# 03.net
KiCad netlist of a schematic drawn in Altium Designer
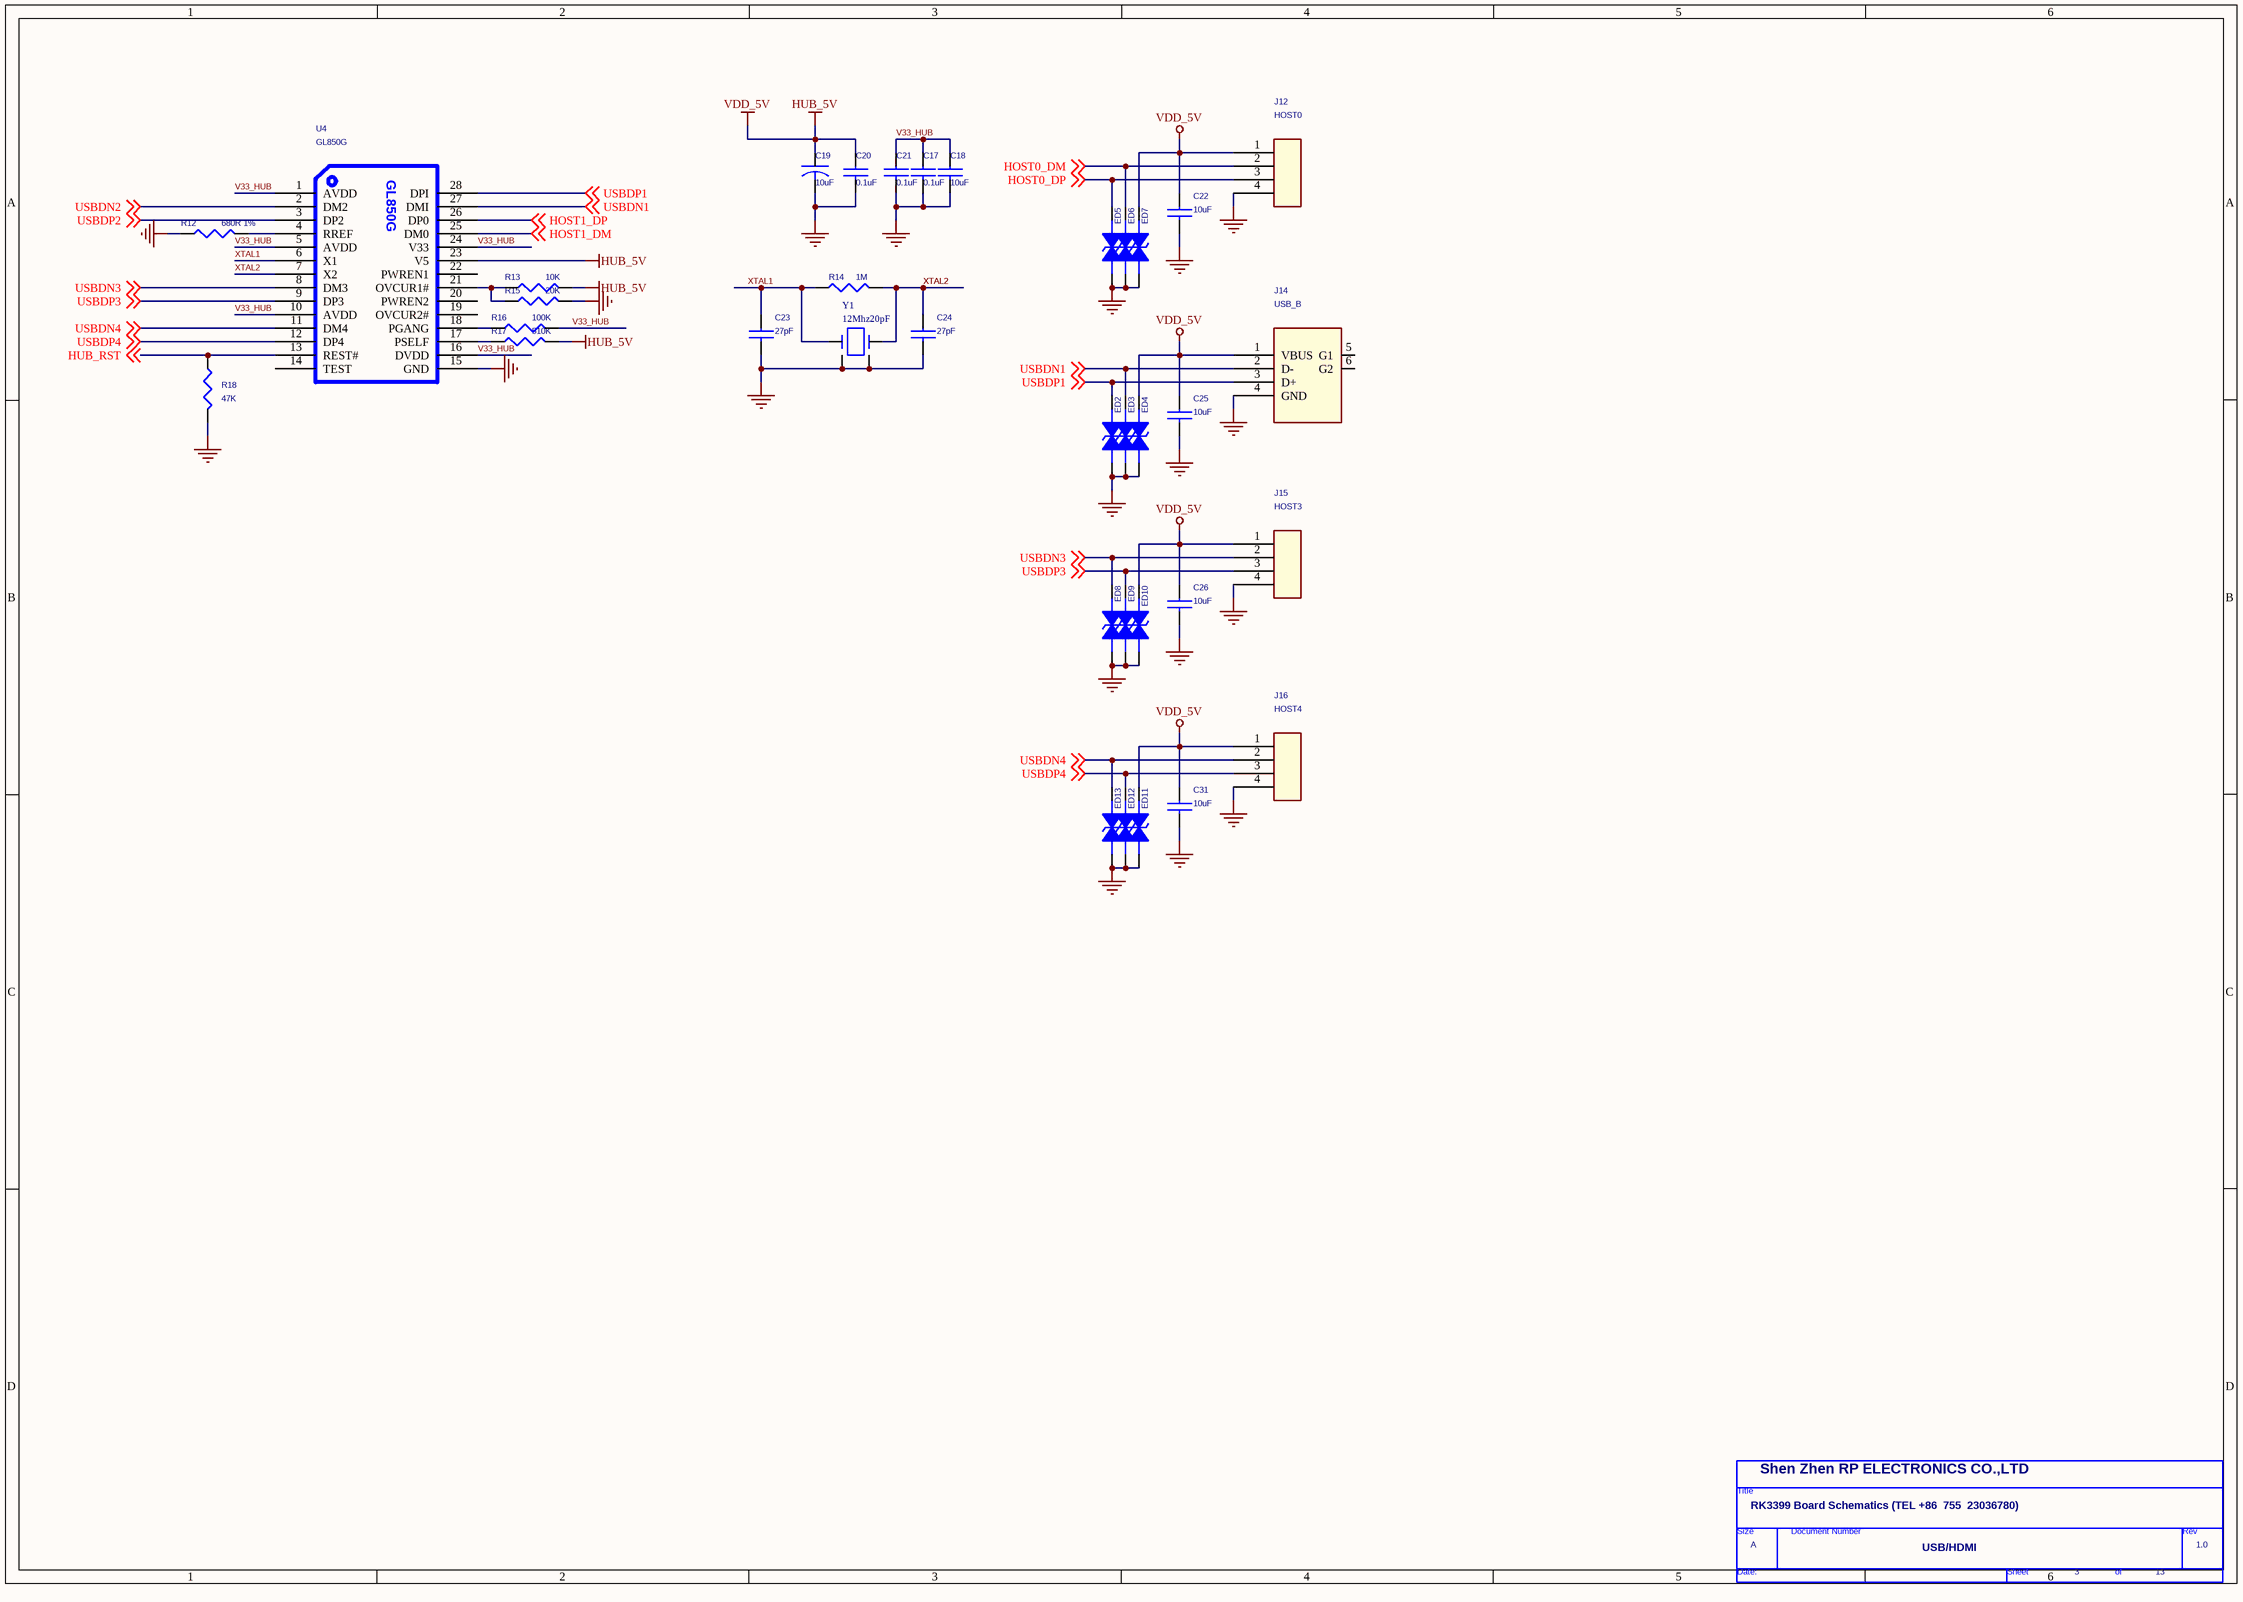
[diagram p0: 03.SchDoc]

(export (version "E")
  (design (tool "Eeschema 10.0.6"))
  (components
    (comp (ref "C17") (value "0.1uF") (footprint "0805C") (libsource (lib "*") (part "CAP NP_Dup5")))
    (comp (ref "C18") (value "10uF") (footprint "0805C") (libsource (lib "*") (part "CAP NP_Dup5")))
    (comp (ref "C19") (value "10uF") (footprint "0805C") (libsource (lib "*") (part "CAP_Dup1")))
    (comp (ref "C20") (value "0.1uF") (footprint "0805C") (libsource (lib "*") (part "CAP NP_Dup5")))
    (comp (ref "C21") (value "0.1uF") (footprint "0805C") (libsource (lib "*") (part "CAP NP_Dup5")))
    (comp (ref "C22") (value "10uF") (footprint "0805C") (libsource (lib "*") (part "CAP NP_Dup8")))
    (comp (ref "C23") (value "27pF") (footprint "0805C") (libsource (lib "*") (part "CAP NP_3_Dup1")))
    (comp (ref "C24") (value "27pF") (footprint "0805C") (libsource (lib "*") (part "CAP NP_3_Dup1")))
    (comp (ref "C25") (value "10uF") (footprint "0805C") (libsource (lib "*") (part "CAP NP_Dup8")))
    (comp (ref "C26") (value "10uF") (footprint "0805C") (libsource (lib "*") (part "CAP NP_Dup8")))
    (comp (ref "C31") (value "10uF") (footprint "0805C") (libsource (lib "*") (part "CAP NP_Dup8")))
    (comp (ref "ED2") (value "ESD") (footprint "SOD-323") (libsource (lib "*") (part "DIODE BI-DIR TRIG")))
    (comp (ref "ED3") (value "ESD") (footprint "SOD-323") (libsource (lib "*") (part "DIODE BI-DIR TRIG")))
    (comp (ref "ED4") (value "ESD") (footprint "SOD-323") (libsource (lib "*") (part "DIODE BI-DIR TRIG")))
    (comp (ref "ED5") (value "ESD") (footprint "SOD-323") (libsource (lib "*") (part "DIODE BI-DIR TRIG")))
    (comp (ref "ED6") (value "ESD") (footprint "SOD-323") (libsource (lib "*") (part "DIODE BI-DIR TRIG")))
    (comp (ref "ED7") (value "ESD") (footprint "SOD-323") (libsource (lib "*") (part "DIODE BI-DIR TRIG")))
    (comp (ref "ED8") (value "ESD") (footprint "SOD-323") (libsource (lib "*") (part "DIODE BI-DIR TRIG")))
    (comp (ref "ED9") (value "ESD") (footprint "SOD-323") (libsource (lib "*") (part "DIODE BI-DIR TRIG")))
    (comp (ref "ED10") (value "ESD") (footprint "SOD-323") (libsource (lib "*") (part "DIODE BI-DIR TRIG")))
    (comp (ref "ED11") (value "ESD") (footprint "SOD-323") (libsource (lib "*") (part "DIODE BI-DIR TRIG")))
    (comp (ref "ED12") (value "ESD") (footprint "SOD-323") (libsource (lib "*") (part "DIODE BI-DIR TRIG")))
    (comp (ref "ED13") (value "ESD") (footprint "SOD-323") (libsource (lib "*") (part "DIODE BI-DIR TRIG")))
    (comp (ref "J12") (value "HOST0") (libsource (lib "*") (part "CON4")))
    (comp (ref "J14") (value "USB_B") (libsource (lib "*") (part "USB_A_1")))
    (comp (ref "J15") (value "HOST3") (libsource (lib "*") (part "CON4")))
    (comp (ref "J16") (value "HOST4") (libsource (lib "*") (part "CON4")))
    (comp (ref "R12") (value "680R 1%") (footprint "0805") (libsource (lib "*") (part "01RES")))
    (comp (ref "R13") (value "10K") (libsource (lib "*") (part "R_1")))
    (comp (ref "R14") (value "1M") (footprint "0805") (libsource (lib "*") (part "RES_0")))
    (comp (ref "R15") (value "20K") (libsource (lib "*") (part "R_1")))
    (comp (ref "R16") (value "100K") (libsource (lib "*") (part "R_1")))
    (comp (ref "R17") (value "510K") (libsource (lib "*") (part "R_1")))
    (comp (ref "R18") (value "47K") (libsource (lib "*") (part "R_1")))
    (comp (ref "U4") (value "GL850G") (libsource (lib "*") (part "FE1_1s_SSOP28_1")))
    (comp (ref "Y1") (value "12Mhz20pF") (libsource (lib "*") (part "CRYSTAL_2")))
  )
  (nets
    (net (code "1") (name "/V33_HUB") (class "Default")
      (node (ref "C17") (pin "1") (pinfunction "1_1") (pintype "passive"))
      (node (ref "C18") (pin "1") (pinfunction "1_1") (pintype "passive"))
      (node (ref "C21") (pin "1") (pinfunction "1_1") (pintype "passive"))
      (node (ref "R16") (pin "2") (pinfunction "2_2") (pintype "passive"))
      (node (ref "U4") (pin "1") (pinfunction "AVDD_1") (pintype "power_in"))
      (node (ref "U4") (pin "10") (pinfunction "AVDD_10") (pintype "power_in"))
      (node (ref "U4") (pin "16") (pinfunction "DVDD_16") (pintype "passive"))
      (node (ref "U4") (pin "24") (pinfunction "V33_24") (pintype "passive"))
      (node (ref "U4") (pin "5") (pinfunction "AVDD_5") (pintype "power_in"))
    )
    (net (code "2") (name "/XTAL1") (class "Default")
      (node (ref "C23") (pin "1") (pinfunction "1_1") (pintype "passive"))
      (node (ref "R14") (pin "2") (pinfunction "2_2") (pintype "passive"))
      (node (ref "U4") (pin "6") (pinfunction "X1_6") (pintype "passive"))
      (node (ref "Y1") (pin "1") (pinfunction "1_1") (pintype "passive"))
    )
    (net (code "3") (name "/XTAL2") (class "Default")
      (node (ref "C24") (pin "1") (pinfunction "1_1") (pintype "passive"))
      (node (ref "R14") (pin "1") (pinfunction "1_1") (pintype "passive"))
      (node (ref "U4") (pin "7") (pinfunction "X2_7") (pintype "passive"))
      (node (ref "Y1") (pin "3") (pinfunction "3_3") (pintype "passive"))
    )
    (net (code "4") (name "GND") (class "Default")
      (node (ref "C17") (pin "2") (pinfunction "2_2") (pintype "passive"))
      (node (ref "C18") (pin "2") (pinfunction "2_2") (pintype "passive"))
      (node (ref "C19") (pin "2") (pinfunction "2_2") (pintype "passive"))
      (node (ref "C20") (pin "2") (pinfunction "2_2") (pintype "passive"))
      (node (ref "C21") (pin "2") (pinfunction "2_2") (pintype "passive"))
      (node (ref "C22") (pin "2") (pinfunction "2_2") (pintype "passive"))
      (node (ref "C23") (pin "2") (pinfunction "2_2") (pintype "passive"))
      (node (ref "C24") (pin "2") (pinfunction "2_2") (pintype "passive"))
      (node (ref "C25") (pin "2") (pinfunction "2_2") (pintype "passive"))
      (node (ref "C26") (pin "2") (pinfunction "2_2") (pintype "passive"))
      (node (ref "C31") (pin "2") (pinfunction "2_2") (pintype "passive"))
      (node (ref "ED10") (pin "2") (pinfunction "2_2") (pintype "passive"))
      (node (ref "ED11") (pin "2") (pinfunction "2_2") (pintype "passive"))
      (node (ref "ED12") (pin "2") (pinfunction "2_2") (pintype "passive"))
      (node (ref "ED13") (pin "2") (pinfunction "2_2") (pintype "passive"))
      (node (ref "ED2") (pin "2") (pinfunction "2_2") (pintype "passive"))
      (node (ref "ED3") (pin "2") (pinfunction "2_2") (pintype "passive"))
      (node (ref "ED4") (pin "2") (pinfunction "2_2") (pintype "passive"))
      (node (ref "ED5") (pin "2") (pinfunction "2_2") (pintype "passive"))
      (node (ref "ED6") (pin "2") (pinfunction "2_2") (pintype "passive"))
      (node (ref "ED7") (pin "2") (pinfunction "2_2") (pintype "passive"))
      (node (ref "ED8") (pin "2") (pinfunction "2_2") (pintype "passive"))
      (node (ref "ED9") (pin "2") (pinfunction "2_2") (pintype "passive"))
      (node (ref "J12") (pin "4") (pinfunction "4_4") (pintype "passive"))
      (node (ref "J14") (pin "4") (pinfunction "GND_4") (pintype "passive"))
      (node (ref "J15") (pin "4") (pinfunction "4_4") (pintype "passive"))
      (node (ref "J16") (pin "4") (pinfunction "4_4") (pintype "passive"))
      (node (ref "R12") (pin "1") (pinfunction "1_1") (pintype "passive"))
      (node (ref "R15") (pin "2") (pinfunction "2_2") (pintype "passive"))
      (node (ref "R18") (pin "2") (pinfunction "2_2") (pintype "passive"))
      (node (ref "U4") (pin "15") (pinfunction "GND_15") (pintype "passive"))
      (node (ref "Y1") (pin "2") (pinfunction "2_2") (pintype "passive"))
      (node (ref "Y1") (pin "4") (pinfunction "4_4") (pintype "passive"))
    )
    (net (code "5") (name "HOST0_DM") (class "Default")
      (node (ref "ED6") (pin "1") (pinfunction "1_1") (pintype "passive"))
      (node (ref "J12") (pin "2") (pinfunction "2_2") (pintype "passive"))
    )
    (net (code "6") (name "HOST0_DP") (class "Default")
      (node (ref "ED5") (pin "1") (pinfunction "1_1") (pintype "passive"))
      (node (ref "J12") (pin "3") (pinfunction "3_3") (pintype "passive"))
    )
    (net (code "7") (name "HOST1_DM") (class "Default")
      (node (ref "U4") (pin "25") (pinfunction "DM0_25") (pintype "passive"))
    )
    (net (code "8") (name "HOST1_DP") (class "Default")
      (node (ref "U4") (pin "26") (pinfunction "DP0_26") (pintype "passive"))
    )
    (net (code "9") (name "HUB_5V") (class "Default")
      (node (ref "C19") (pin "1") (pinfunction "1_1") (pintype "passive"))
      (node (ref "C20") (pin "1") (pinfunction "1_1") (pintype "passive"))
      (node (ref "C22") (pin "1") (pinfunction "1_1") (pintype "passive"))
      (node (ref "C25") (pin "1") (pinfunction "1_1") (pintype "passive"))
      (node (ref "C26") (pin "1") (pinfunction "1_1") (pintype "passive"))
      (node (ref "C31") (pin "1") (pinfunction "1_1") (pintype "passive"))
      (node (ref "ED10") (pin "1") (pinfunction "1_1") (pintype "passive"))
      (node (ref "ED11") (pin "1") (pinfunction "1_1") (pintype "passive"))
      (node (ref "ED4") (pin "1") (pinfunction "1_1") (pintype "passive"))
      (node (ref "ED7") (pin "1") (pinfunction "1_1") (pintype "passive"))
      (node (ref "J12") (pin "1") (pinfunction "1_1") (pintype "passive"))
      (node (ref "J14") (pin "1") (pinfunction "VBUS_1") (pintype "passive"))
      (node (ref "J15") (pin "1") (pinfunction "1_1") (pintype "passive"))
      (node (ref "J16") (pin "1") (pinfunction "1_1") (pintype "passive"))
      (node (ref "R13") (pin "2") (pinfunction "2_2") (pintype "passive"))
      (node (ref "R17") (pin "2") (pinfunction "2_2") (pintype "passive"))
      (node (ref "U4") (pin "23") (pinfunction "V5_23") (pintype "passive"))
    )
    (net (code "10") (name "HUB_RST") (class "Default")
      (node (ref "R18") (pin "1") (pinfunction "1_1") (pintype "passive"))
      (node (ref "U4") (pin "13") (pinfunction "REST#_13") (pintype "passive"))
    )
    (net (code "11") (name "Net-(U4-OVCUR1#)") (class "Default")
      (node (ref "R13") (pin "1") (pinfunction "1_1") (pintype "passive"))
      (node (ref "R15") (pin "1") (pinfunction "1_1") (pintype "passive"))
      (node (ref "U4") (pin "21") (pinfunction "OVCUR1#_21") (pintype "passive"))
    )
    (net (code "12") (name "Net-(U4-PGANG)") (class "Default")
      (node (ref "R16") (pin "1") (pinfunction "1_1") (pintype "passive"))
      (node (ref "U4") (pin "18") (pinfunction "PGANG_18") (pintype "passive"))
    )
    (net (code "13") (name "Net-(U4-PSELF)") (class "Default")
      (node (ref "R17") (pin "1") (pinfunction "1_1") (pintype "passive"))
      (node (ref "U4") (pin "17") (pinfunction "PSELF_17") (pintype "passive"))
    )
    (net (code "14") (name "Net-(U4-RREF)") (class "Default")
      (node (ref "R12") (pin "2") (pinfunction "2_2") (pintype "passive"))
      (node (ref "U4") (pin "4") (pinfunction "RREF_4") (pintype "passive"))
    )
    (net (code "15") (name "USBDN1") (class "Default")
      (node (ref "ED3") (pin "1") (pinfunction "1_1") (pintype "passive"))
      (node (ref "J14") (pin "2") (pinfunction "D-_2") (pintype "passive"))
      (node (ref "U4") (pin "27") (pinfunction "DMI_27") (pintype "passive"))
    )
    (net (code "16") (name "USBDN2") (class "Default")
      (node (ref "U4") (pin "2") (pinfunction "DM2_2") (pintype "passive"))
    )
    (net (code "17") (name "USBDN3") (class "Default")
      (node (ref "ED8") (pin "1") (pinfunction "1_1") (pintype "passive"))
      (node (ref "J15") (pin "2") (pinfunction "2_2") (pintype "passive"))
      (node (ref "U4") (pin "8") (pinfunction "DM3_8") (pintype "passive"))
    )
    (net (code "18") (name "USBDN4") (class "Default")
      (node (ref "ED13") (pin "1") (pinfunction "1_1") (pintype "passive"))
      (node (ref "J16") (pin "2") (pinfunction "2_2") (pintype "passive"))
      (node (ref "U4") (pin "11") (pinfunction "DM4_11") (pintype "passive"))
    )
    (net (code "19") (name "USBDP1") (class "Default")
      (node (ref "ED2") (pin "1") (pinfunction "1_1") (pintype "passive"))
      (node (ref "J14") (pin "3") (pinfunction "D+_3") (pintype "passive"))
      (node (ref "U4") (pin "28") (pinfunction "DPI_28") (pintype "passive"))
    )
    (net (code "20") (name "USBDP2") (class "Default")
      (node (ref "U4") (pin "3") (pinfunction "DP2_3") (pintype "passive"))
    )
    (net (code "21") (name "USBDP3") (class "Default")
      (node (ref "ED9") (pin "1") (pinfunction "1_1") (pintype "passive"))
      (node (ref "J15") (pin "3") (pinfunction "3_3") (pintype "passive"))
      (node (ref "U4") (pin "9") (pinfunction "DP3_9") (pintype "passive"))
    )
    (net (code "22") (name "USBDP4") (class "Default")
      (node (ref "ED12") (pin "1") (pinfunction "1_1") (pintype "passive"))
      (node (ref "J16") (pin "3") (pinfunction "3_3") (pintype "passive"))
      (node (ref "U4") (pin "12") (pinfunction "DP4_12") (pintype "passive"))
    )
    (net (code "23") (name "unconnected-(J14-G1-Pad5)") (class "Default")
      (node (ref "J14") (pin "5") (pinfunction "G1_5") (pintype "passive"))
    )
    (net (code "24") (name "unconnected-(J14-G2-Pad6)") (class "Default")
      (node (ref "J14") (pin "6") (pinfunction "G2_6") (pintype "passive"))
    )
    (net (code "25") (name "unconnected-(U4-OVCUR2#-Pad19)") (class "Default")
      (node (ref "U4") (pin "19") (pinfunction "OVCUR2#_19") (pintype "passive"))
    )
    (net (code "26") (name "unconnected-(U4-PWREN1-Pad22)") (class "Default")
      (node (ref "U4") (pin "22") (pinfunction "PWREN1_22") (pintype "passive"))
    )
    (net (code "27") (name "unconnected-(U4-PWREN2-Pad20)") (class "Default")
      (node (ref "U4") (pin "20") (pinfunction "PWREN2_20") (pintype "passive"))
    )
    (net (code "28") (name "unconnected-(U4-TEST-Pad14)") (class "Default")
      (node (ref "U4") (pin "14") (pinfunction "TEST_14") (pintype "passive"))
    )
  )
)
